# Sheet1.net
KiCad netlist of a schematic drawn in Altium Designer
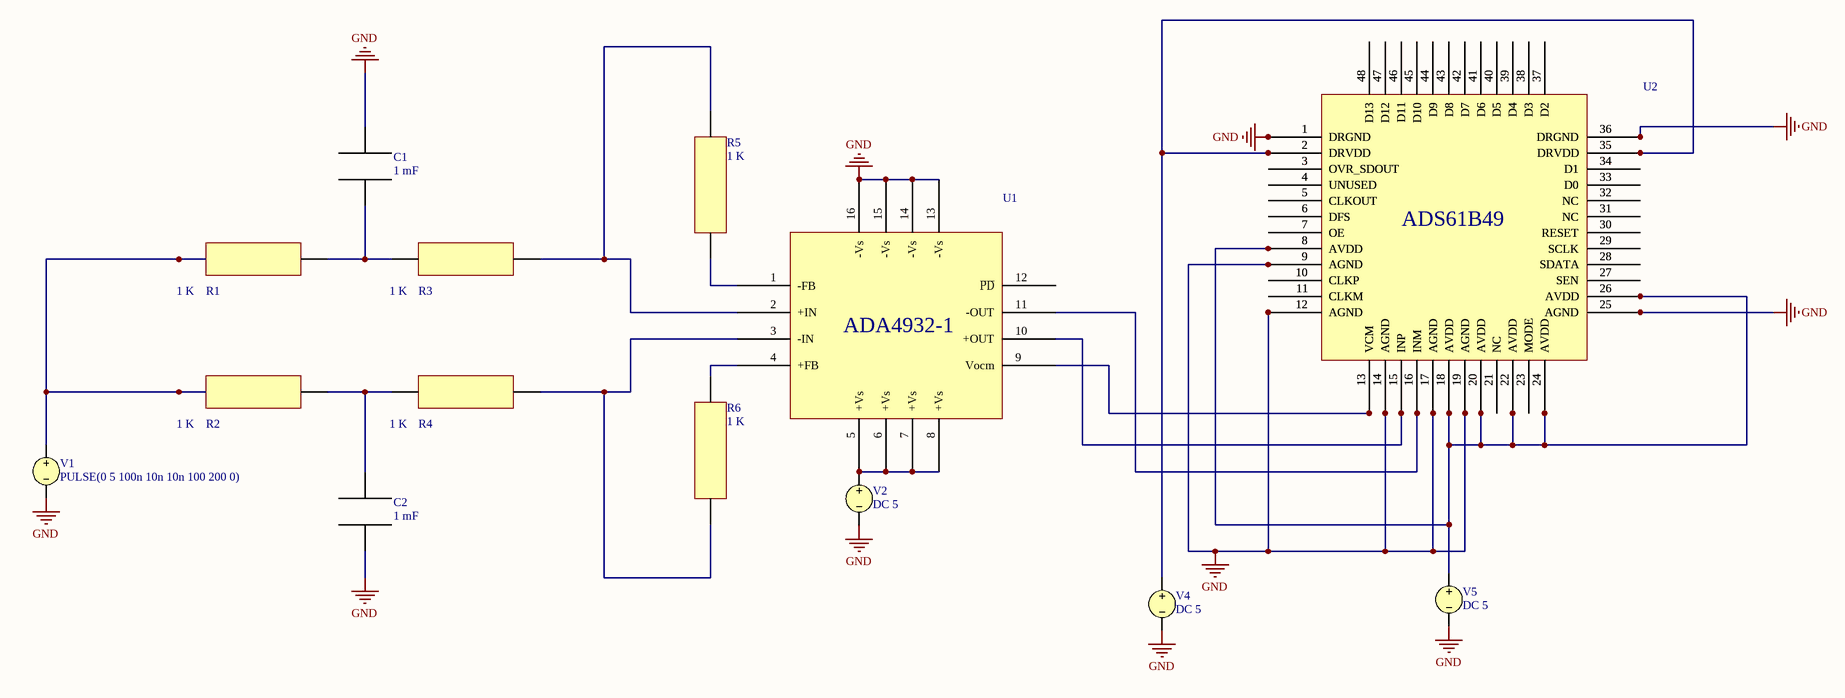
[diagram p0: Sheet1.SchDoc]

(export (version "E")
  (design (tool "Eeschema 10.0.6"))
  (components
    (comp (ref "C1")
      (value "Capacitor")
      (footprint "PCB_C")
      (fields (field (name "CAPACITANCE") "1 mF"))
      (libsource (lib "V_5") (part "Capacitor"))
    )
    (comp (ref "C2")
      (value "Capacitor")
      (footprint "PCB_C")
      (fields (field (name "CAPACITANCE") "1 mF"))
      (libsource (lib "V_5") (part "Capacitor"))
    )
    (comp (ref "R1")
      (value "Resistor")
      (footprint "PCB_R")
      (fields (field (name "RESISTANCE") "1 K"))
      (libsource (lib "V_5") (part "Resistor"))
    )
    (comp (ref "R2")
      (value "Resistor")
      (footprint "PCB_R")
      (fields (field (name "RESISTANCE") "1 K"))
      (libsource (lib "V_5") (part "Resistor"))
    )
    (comp (ref "R3")
      (value "Resistor")
      (footprint "PCB_R")
      (fields (field (name "RESISTANCE") "1 K"))
      (libsource (lib "V_5") (part "Resistor"))
    )
    (comp (ref "R4")
      (value "Resistor")
      (footprint "PCB_R")
      (fields (field (name "RESISTANCE") "1 K"))
      (libsource (lib "V_5") (part "Resistor"))
    )
    (comp (ref "R5")
      (value "Resistor")
      (footprint "PCB_R")
      (fields (field (name "RESISTANCE") "1 K"))
      (libsource (lib "") (part "Resistor_1"))
    )
    (comp (ref "R6")
      (value "Resistor")
      (footprint "PCB_R")
      (fields (field (name "RESISTANCE") "1 K"))
      (libsource (lib "") (part "Resistor_1"))
    )
    (comp (ref "U1")
      (value "Operational_amplifier")
      (footprint "PCB_OA")
      (libsource (lib "V_5") (part "Operational_amplifier"))
    )
    (comp (ref "U2")
      (value "Analog-to-Digital_Converter")
      (footprint "PCB_ADC")
      (libsource (lib "V_5") (part "Analog-to-Digital_Converter"))
    )
    (comp (ref "V1")
      (value "PULSE(0 5 100n 10n 10n 100 200 0)")
      (description "Voltage Source")
      (fields (field (name "PUBLISHER") "Altium Limited"))
      (libsource (lib "Simulation Generic Components") (part "VSRC"))
    )
    (comp (ref "V2")
      (value "DC 5")
      (description "Voltage Source")
      (fields (field (name "PUBLISHER") "Altium Limited"))
      (libsource (lib "Simulation Generic Components") (part "VSRC"))
    )
    (comp (ref "V4")
      (value "DC 5")
      (description "Voltage Source")
      (fields (field (name "PUBLISHER") "Altium Limited"))
      (libsource (lib "Simulation Generic Components") (part "VSRC"))
    )
    (comp (ref "V5")
      (value "DC 5")
      (description "Voltage Source")
      (fields (field (name "PUBLISHER") "Altium Limited"))
      (libsource (lib "Simulation Generic Components") (part "VSRC"))
    )
  )
  (nets
    (net (code "1") (name "GND") (class "Default")
      (node (ref "C1") (pin "2") (pinfunction "2_2") (pintype "passive"))
      (node (ref "C2") (pin "1") (pinfunction "1_1") (pintype "passive"))
      (node (ref "U1") (pin "13") (pinfunction "-Vs_13") (pintype "passive"))
      (node (ref "U1") (pin "14") (pinfunction "-Vs_14") (pintype "passive"))
      (node (ref "U1") (pin "15") (pinfunction "-Vs_15") (pintype "passive"))
      (node (ref "U1") (pin "16") (pinfunction "-Vs_16") (pintype "passive"))
      (node (ref "U2") (pin "1") (pinfunction "DRGND_1") (pintype "passive"))
      (node (ref "U2") (pin "12") (pinfunction "AGND_12") (pintype "passive"))
      (node (ref "U2") (pin "14") (pinfunction "AGND_14") (pintype "passive"))
      (node (ref "U2") (pin "17") (pinfunction "AGND_17") (pintype "passive"))
      (node (ref "U2") (pin "19") (pinfunction "AGND_19") (pintype "passive"))
      (node (ref "U2") (pin "25") (pinfunction "AGND_25") (pintype "passive"))
      (node (ref "U2") (pin "36") (pinfunction "DRGND_36") (pintype "passive"))
      (node (ref "U2") (pin "9") (pinfunction "AGND_9") (pintype "passive"))
      (node (ref "V1") (pin "2") (pinfunction "2_2") (pintype "passive"))
      (node (ref "V2") (pin "2") (pinfunction "2_2") (pintype "passive"))
      (node (ref "V4") (pin "2") (pinfunction "2_2") (pintype "passive"))
      (node (ref "V5") (pin "2") (pinfunction "2_2") (pintype "passive"))
    )
    (net (code "2") (name "Net-(C1-Pad1)") (class "Default")
      (node (ref "C1") (pin "1") (pinfunction "1_1") (pintype "passive"))
      (node (ref "R1") (pin "2") (pinfunction "2_2") (pintype "passive"))
      (node (ref "R3") (pin "1") (pinfunction "1_1") (pintype "passive"))
    )
    (net (code "3") (name "Net-(C2-Pad2)") (class "Default")
      (node (ref "C2") (pin "2") (pinfunction "2_2") (pintype "passive"))
      (node (ref "R2") (pin "2") (pinfunction "2_2") (pintype "passive"))
      (node (ref "R4") (pin "1") (pinfunction "1_1") (pintype "passive"))
    )
    (net (code "4") (name "Net-(R1-Pad1)") (class "Default")
      (node (ref "R1") (pin "1") (pinfunction "1_1") (pintype "passive"))
      (node (ref "R2") (pin "1") (pinfunction "1_1") (pintype "passive"))
      (node (ref "V1") (pin "1") (pinfunction "1_1") (pintype "passive"))
    )
    (net (code "5") (name "Net-(U1-+FB)") (class "Default")
      (node (ref "R6") (pin "2") (pinfunction "2_2") (pintype "passive"))
      (node (ref "U1") (pin "4") (pinfunction "+FB_4") (pintype "passive"))
    )
    (net (code "6") (name "Net-(U1-+IN)") (class "Default")
      (node (ref "R3") (pin "2") (pinfunction "2_2") (pintype "passive"))
      (node (ref "R5") (pin "2") (pinfunction "2_2") (pintype "passive"))
      (node (ref "U1") (pin "2") (pinfunction "+IN_2") (pintype "passive"))
    )
    (net (code "7") (name "Net-(U1-+OUT)") (class "Default")
      (node (ref "U1") (pin "10") (pinfunction "+OUT_10") (pintype "passive"))
      (node (ref "U2") (pin "15") (pinfunction "INP_15") (pintype "passive"))
    )
    (net (code "8") (name "Net-(U1-+Vs-Pad5)") (class "Default")
      (node (ref "U1") (pin "5") (pinfunction "+Vs_5") (pintype "passive"))
      (node (ref "U1") (pin "6") (pinfunction "+Vs_6") (pintype "passive"))
      (node (ref "U1") (pin "7") (pinfunction "+Vs_7") (pintype "passive"))
      (node (ref "U1") (pin "8") (pinfunction "+Vs_8") (pintype "passive"))
      (node (ref "V2") (pin "1") (pinfunction "1_1") (pintype "passive"))
    )
    (net (code "9") (name "Net-(U1--FB)") (class "Default")
      (node (ref "R5") (pin "1") (pinfunction "1_1") (pintype "passive"))
      (node (ref "U1") (pin "1") (pinfunction "-FB_1") (pintype "passive"))
    )
    (net (code "10") (name "Net-(U1--IN)") (class "Default")
      (node (ref "R4") (pin "2") (pinfunction "2_2") (pintype "passive"))
      (node (ref "R6") (pin "1") (pinfunction "1_1") (pintype "passive"))
      (node (ref "U1") (pin "3") (pinfunction "-IN_3") (pintype "passive"))
    )
    (net (code "11") (name "Net-(U1--OUT)") (class "Default")
      (node (ref "U1") (pin "11") (pinfunction "-OUT_11") (pintype "passive"))
      (node (ref "U2") (pin "16") (pinfunction "INM_16") (pintype "passive"))
    )
    (net (code "12") (name "Net-(U1-Vocm)") (class "Default")
      (node (ref "U1") (pin "9") (pinfunction "Vocm_9") (pintype "passive"))
      (node (ref "U2") (pin "13") (pinfunction "VCM_13") (pintype "passive"))
    )
    (net (code "13") (name "Net-(U2-AVDD-Pad18)") (class "Default")
      (node (ref "U2") (pin "18") (pinfunction "AVDD_18") (pintype "passive"))
      (node (ref "U2") (pin "20") (pinfunction "AVDD_20") (pintype "passive"))
      (node (ref "U2") (pin "22") (pinfunction "AVDD_22") (pintype "passive"))
      (node (ref "U2") (pin "24") (pinfunction "AVDD_24") (pintype "passive"))
      (node (ref "U2") (pin "26") (pinfunction "AVDD_26") (pintype "passive"))
      (node (ref "U2") (pin "8") (pinfunction "AVDD_8") (pintype "passive"))
      (node (ref "V5") (pin "1") (pinfunction "1_1") (pintype "passive"))
    )
    (net (code "14") (name "Net-(U2-CLKM)") (class "Default")
      (node (ref "U2") (pin "11") (pinfunction "CLKM_11") (pintype "passive"))
    )
    (net (code "15") (name "Net-(U2-CLKOUT)") (class "Default")
      (node (ref "U2") (pin "5") (pinfunction "CLKOUT_5") (pintype "passive"))
    )
    (net (code "16") (name "Net-(U2-CLKP)") (class "Default")
      (node (ref "U2") (pin "10") (pinfunction "CLKP_10") (pintype "passive"))
    )
    (net (code "17") (name "Net-(U2-D0)") (class "Default")
      (node (ref "U2") (pin "33") (pinfunction "D0_33") (pintype "passive"))
    )
    (net (code "18") (name "Net-(U2-D1)") (class "Default")
      (node (ref "U2") (pin "34") (pinfunction "D1_34") (pintype "passive"))
    )
    (net (code "19") (name "Net-(U2-D2)") (class "Default")
      (node (ref "U2") (pin "37") (pinfunction "D2_37") (pintype "passive"))
    )
    (net (code "20") (name "Net-(U2-D3)") (class "Default")
      (node (ref "U2") (pin "38") (pinfunction "D3_38") (pintype "passive"))
    )
    (net (code "21") (name "Net-(U2-D4)") (class "Default")
      (node (ref "U2") (pin "39") (pinfunction "D4_39") (pintype "passive"))
    )
    (net (code "22") (name "Net-(U2-D5)") (class "Default")
      (node (ref "U2") (pin "40") (pinfunction "D5_40") (pintype "passive"))
    )
    (net (code "23") (name "Net-(U2-D6)") (class "Default")
      (node (ref "U2") (pin "41") (pinfunction "D6_41") (pintype "passive"))
    )
    (net (code "24") (name "Net-(U2-D7)") (class "Default")
      (node (ref "U2") (pin "42") (pinfunction "D7_42") (pintype "passive"))
    )
    (net (code "25") (name "Net-(U2-D8)") (class "Default")
      (node (ref "U2") (pin "43") (pinfunction "D8_43") (pintype "passive"))
    )
    (net (code "26") (name "Net-(U2-D9)") (class "Default")
      (node (ref "U2") (pin "44") (pinfunction "D9_44") (pintype "passive"))
    )
    (net (code "27") (name "Net-(U2-D10)") (class "Default")
      (node (ref "U2") (pin "45") (pinfunction "D10_45") (pintype "passive"))
    )
    (net (code "28") (name "Net-(U2-D11)") (class "Default")
      (node (ref "U2") (pin "46") (pinfunction "D11_46") (pintype "passive"))
    )
    (net (code "29") (name "Net-(U2-D12)") (class "Default")
      (node (ref "U2") (pin "47") (pinfunction "D12_47") (pintype "passive"))
    )
    (net (code "30") (name "Net-(U2-D13)") (class "Default")
      (node (ref "U2") (pin "48") (pinfunction "D13_48") (pintype "passive"))
    )
    (net (code "31") (name "Net-(U2-DFS)") (class "Default")
      (node (ref "U2") (pin "6") (pinfunction "DFS_6") (pintype "passive"))
    )
    (net (code "32") (name "Net-(U2-DRVDD-Pad2)") (class "Default")
      (node (ref "U2") (pin "2") (pinfunction "DRVDD_2") (pintype "passive"))
      (node (ref "U2") (pin "35") (pinfunction "DRVDD_35") (pintype "passive"))
      (node (ref "V4") (pin "1") (pinfunction "1_1") (pintype "passive"))
    )
    (net (code "33") (name "Net-(U2-MODE)") (class "Default")
      (node (ref "U2") (pin "23") (pinfunction "MODE_23") (pintype "passive"))
    )
    (net (code "34") (name "Net-(U2-NC-Pad21)") (class "Default")
      (node (ref "U2") (pin "21") (pinfunction "NC_21") (pintype "passive"))
    )
    (net (code "35") (name "Net-(U2-NC-Pad31)") (class "Default")
      (node (ref "U2") (pin "31") (pinfunction "NC_31") (pintype "passive"))
    )
    (net (code "36") (name "Net-(U2-NC-Pad32)") (class "Default")
      (node (ref "U2") (pin "32") (pinfunction "NC_32") (pintype "passive"))
    )
    (net (code "37") (name "Net-(U2-OE)") (class "Default")
      (node (ref "U2") (pin "7") (pinfunction "OE_7") (pintype "passive"))
    )
    (net (code "38") (name "Net-(U2-OVR_SDOUT)") (class "Default")
      (node (ref "U2") (pin "3") (pinfunction "OVR_SDOUT_3") (pintype "passive"))
    )
    (net (code "39") (name "Net-(U2-RESET)") (class "Default")
      (node (ref "U2") (pin "30") (pinfunction "RESET_30") (pintype "passive"))
    )
    (net (code "40") (name "Net-(U2-SCLK)") (class "Default")
      (node (ref "U2") (pin "29") (pinfunction "SCLK_29") (pintype "passive"))
    )
    (net (code "41") (name "Net-(U2-SDATA)") (class "Default")
      (node (ref "U2") (pin "28") (pinfunction "SDATA_28") (pintype "passive"))
    )
    (net (code "42") (name "Net-(U2-SEN)") (class "Default")
      (node (ref "U2") (pin "27") (pinfunction "SEN_27") (pintype "passive"))
    )
    (net (code "43") (name "Net-(U2-UNUSED)") (class "Default")
      (node (ref "U2") (pin "4") (pinfunction "UNUSED_4") (pintype "passive"))
    )
    (net (code "44") (name "unconnected-(U1-P̅D̅-Pad12)") (class "Default")
      (node (ref "U1") (pin "12") (pinfunction "P̅D̅_12") (pintype "passive"))
    )
  )
)
